# Connectors.net
KiCad netlist of a schematic drawn in Altium Designer
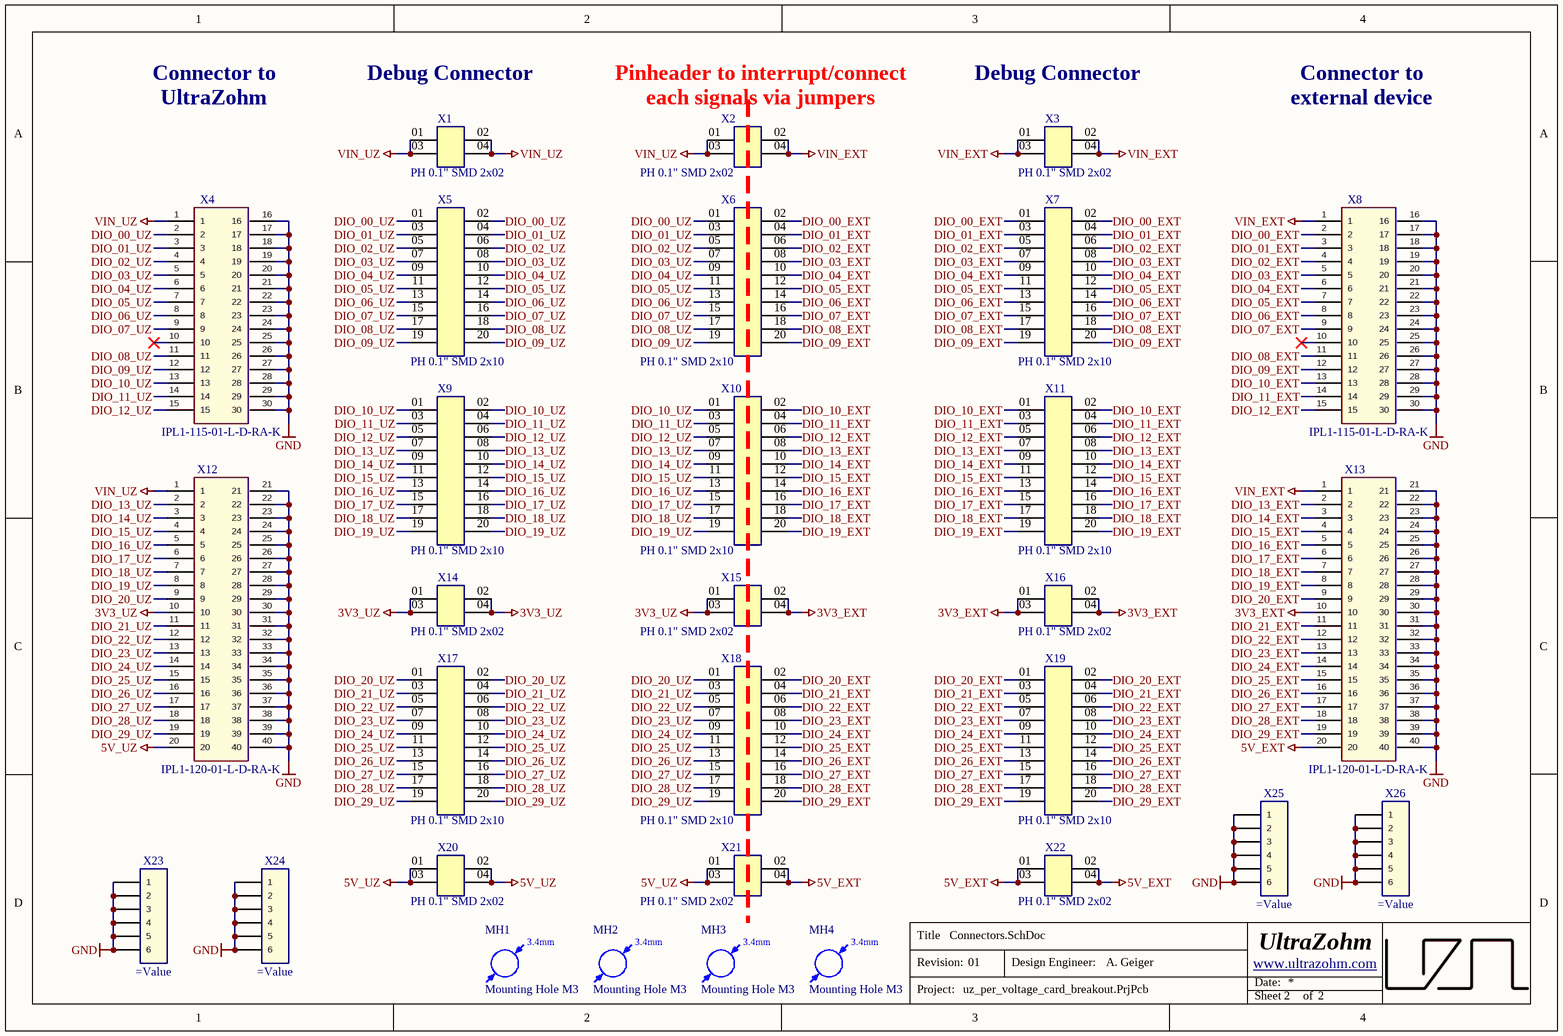
[diagram p0: Connectors.SchDoc]

(export (version "E")
  (design (tool "Eeschema 10.0.6"))
  (components
    (comp (ref "MH1")
      (value "Mounting Hole M3")
      (footprint "MH_3.4")
      (description "Mounting Hole")
      (fields (field (name "CREATED FROM") "MHlatky"))
      (libsource (lib "user") (part "Mounting Hole"))
    )
    (comp (ref "MH2")
      (value "Mounting Hole M3")
      (footprint "MH_3.4")
      (description "Mounting Hole")
      (fields (field (name "CREATED FROM") "MHlatky"))
      (libsource (lib "user") (part "Mounting Hole"))
    )
    (comp (ref "MH3")
      (value "Mounting Hole M3")
      (footprint "MH_3.4")
      (description "Mounting Hole")
      (fields (field (name "CREATED FROM") "MHlatky"))
      (libsource (lib "user") (part "Mounting Hole"))
    )
    (comp (ref "MH4")
      (value "Mounting Hole M3")
      (footprint "MH_3.4")
      (description "Mounting Hole")
      (fields (field (name "CREATED FROM") "MHlatky"))
      (libsource (lib "user") (part "Mounting Hole"))
    )
    (comp (ref "X1")
      (value "PH 0.1\" SMD 2x02")
      (footprint "TSM-102-01-L-DV")
      (description "0.1\" Double-row Pin Header, 90°-to-PCB SMD, 2x02 Pins, 250V, 3A")
      (fields
        (field (name "MANUFACTURER PART NUMBER") "UZgen_Conn_PinHead_2x02_SMD_100mil_90deg")
        (field (name "MANUFACTURER") "UZgen")
        (field (name "CREATED FROM") "UZgenTool")
      )
      (libsource (lib "user") (part "PinHeader_2x02"))
    )
    (comp (ref "X2")
      (value "PH 0.1\" SMD 2x02")
      (footprint "TSM-102-01-L-DV")
      (description "0.1\" Double-row Pin Header, 90°-to-PCB SMD, 2x02 Pins, 250V, 3A")
      (fields
        (field (name "MANUFACTURER PART NUMBER") "UZgen_Conn_PinHead_2x02_SMD_100mil_90deg")
        (field (name "MANUFACTURER") "UZgen")
        (field (name "CREATED FROM") "UZgenTool")
      )
      (libsource (lib "user") (part "PinHeader_2x02"))
    )
    (comp (ref "X3")
      (value "PH 0.1\" SMD 2x02")
      (footprint "TSM-102-01-L-DV")
      (description "0.1\" Double-row Pin Header, 90°-to-PCB SMD, 2x02 Pins, 250V, 3A")
      (fields
        (field (name "MANUFACTURER PART NUMBER") "UZgen_Conn_PinHead_2x02_SMD_100mil_90deg")
        (field (name "MANUFACTURER") "UZgen")
        (field (name "CREATED FROM") "UZgenTool")
      )
      (libsource (lib "user") (part "PinHeader_2x02"))
    )
    (comp (ref "X4")
      (value "IPL1-115-01-L-D-RA-K")
      (footprint "IPL1-115-01-XX-D-RA")
      (description "Terminal Assembly, Double Row, Right Angle, Thru-Hole, 2.54 mm x 2.54 mm Pitch, 30 Pins")
      (fields (field (name "MANUFACTURER") "SAMTEC") (field (name "CREATED FROM") "TWendt"))
      (libsource (lib "user") (part "IPL1-115-01-XX-D-RA"))
    )
    (comp (ref "X5")
      (value "PH 0.1\" SMD 2x10")
      (footprint "TSM-110-01-L-DV")
      (description "0.1\" Double-row Pin Header, 90°-to-PCB SMD, 2x10 Pins, 250V, 3A")
      (fields
        (field (name "MANUFACTURER PART NUMBER") "UZgen_Conn_PinHead_2x10_SMD_100mil_90deg")
        (field (name "MANUFACTURER") "UZgen")
        (field (name "CREATED FROM") "UZgenTool")
      )
      (libsource (lib "user") (part "PinHeader_2x10"))
    )
    (comp (ref "X6")
      (value "PH 0.1\" SMD 2x10")
      (footprint "TSM-110-01-L-DV")
      (description "0.1\" Double-row Pin Header, 90°-to-PCB SMD, 2x10 Pins, 250V, 3A")
      (fields
        (field (name "MANUFACTURER PART NUMBER") "UZgen_Conn_PinHead_2x10_SMD_100mil_90deg")
        (field (name "MANUFACTURER") "UZgen")
        (field (name "CREATED FROM") "UZgenTool")
      )
      (libsource (lib "user") (part "PinHeader_2x10"))
    )
    (comp (ref "X7")
      (value "PH 0.1\" SMD 2x10")
      (footprint "TSM-110-01-L-DV")
      (description "0.1\" Double-row Pin Header, 90°-to-PCB SMD, 2x10 Pins, 250V, 3A")
      (fields
        (field (name "MANUFACTURER PART NUMBER") "UZgen_Conn_PinHead_2x10_SMD_100mil_90deg")
        (field (name "MANUFACTURER") "UZgen")
        (field (name "CREATED FROM") "UZgenTool")
      )
      (libsource (lib "user") (part "PinHeader_2x10"))
    )
    (comp (ref "X8")
      (value "IPL1-115-01-L-D-RA-K")
      (footprint "IPL1-115-01-XX-D-RA")
      (description "Terminal Assembly, Double Row, Right Angle, Thru-Hole, 2.54 mm x 2.54 mm Pitch, 30 Pins")
      (fields (field (name "MANUFACTURER") "SAMTEC") (field (name "CREATED FROM") "TWendt"))
      (libsource (lib "user") (part "IPL1-115-01-XX-D-RA"))
    )
    (comp (ref "X9")
      (value "PH 0.1\" SMD 2x10")
      (footprint "TSM-110-01-L-DV")
      (description "0.1\" Double-row Pin Header, 90°-to-PCB SMD, 2x10 Pins, 250V, 3A")
      (fields
        (field (name "MANUFACTURER PART NUMBER") "UZgen_Conn_PinHead_2x10_SMD_100mil_90deg")
        (field (name "MANUFACTURER") "UZgen")
        (field (name "CREATED FROM") "UZgenTool")
      )
      (libsource (lib "user") (part "PinHeader_2x10"))
    )
    (comp (ref "X10")
      (value "PH 0.1\" SMD 2x10")
      (footprint "TSM-110-01-L-DV")
      (description "0.1\" Double-row Pin Header, 90°-to-PCB SMD, 2x10 Pins, 250V, 3A")
      (fields
        (field (name "MANUFACTURER PART NUMBER") "UZgen_Conn_PinHead_2x10_SMD_100mil_90deg")
        (field (name "MANUFACTURER") "UZgen")
        (field (name "CREATED FROM") "UZgenTool")
      )
      (libsource (lib "user") (part "PinHeader_2x10"))
    )
    (comp (ref "X11")
      (value "PH 0.1\" SMD 2x10")
      (footprint "TSM-110-01-L-DV")
      (description "0.1\" Double-row Pin Header, 90°-to-PCB SMD, 2x10 Pins, 250V, 3A")
      (fields
        (field (name "MANUFACTURER PART NUMBER") "UZgen_Conn_PinHead_2x10_SMD_100mil_90deg")
        (field (name "MANUFACTURER") "UZgen")
        (field (name "CREATED FROM") "UZgenTool")
      )
      (libsource (lib "user") (part "PinHeader_2x10"))
    )
    (comp (ref "X12")
      (value "IPL1-120-01-L-D-RA-K")
      (footprint "IPL1-120-01-XX-D-RA")
      (description "Terminal Assembly, Double Row, Right Angle, Thru-Hole, 2.54 mm x 2.54 mm Pitch, 40 Pins")
      (fields (field (name "MANUFACTURER") "SAMTEC") (field (name "CREATED FROM") "TWendt"))
      (libsource (lib "user") (part "IPL1-120-01-XX-D-RA"))
    )
    (comp (ref "X13")
      (value "IPL1-120-01-L-D-RA-K")
      (footprint "IPL1-120-01-XX-D-RA")
      (description "Terminal Assembly, Double Row, Right Angle, Thru-Hole, 2.54 mm x 2.54 mm Pitch, 40 Pins")
      (fields (field (name "MANUFACTURER") "SAMTEC") (field (name "CREATED FROM") "TWendt"))
      (libsource (lib "user") (part "IPL1-120-01-XX-D-RA"))
    )
    (comp (ref "X14")
      (value "PH 0.1\" SMD 2x02")
      (footprint "TSM-102-01-L-DV")
      (description "0.1\" Double-row Pin Header, 90°-to-PCB SMD, 2x02 Pins, 250V, 3A")
      (fields
        (field (name "MANUFACTURER PART NUMBER") "UZgen_Conn_PinHead_2x02_SMD_100mil_90deg")
        (field (name "MANUFACTURER") "UZgen")
        (field (name "CREATED FROM") "UZgenTool")
      )
      (libsource (lib "user") (part "PinHeader_2x02"))
    )
    (comp (ref "X15")
      (value "PH 0.1\" SMD 2x02")
      (footprint "TSM-102-01-L-DV")
      (description "0.1\" Double-row Pin Header, 90°-to-PCB SMD, 2x02 Pins, 250V, 3A")
      (fields
        (field (name "MANUFACTURER PART NUMBER") "UZgen_Conn_PinHead_2x02_SMD_100mil_90deg")
        (field (name "MANUFACTURER") "UZgen")
        (field (name "CREATED FROM") "UZgenTool")
      )
      (libsource (lib "user") (part "PinHeader_2x02"))
    )
    (comp (ref "X16")
      (value "PH 0.1\" SMD 2x02")
      (footprint "TSM-102-01-L-DV")
      (description "0.1\" Double-row Pin Header, 90°-to-PCB SMD, 2x02 Pins, 250V, 3A")
      (fields
        (field (name "MANUFACTURER PART NUMBER") "UZgen_Conn_PinHead_2x02_SMD_100mil_90deg")
        (field (name "MANUFACTURER") "UZgen")
        (field (name "CREATED FROM") "UZgenTool")
      )
      (libsource (lib "user") (part "PinHeader_2x02"))
    )
    (comp (ref "X17")
      (value "PH 0.1\" SMD 2x10")
      (footprint "TSM-110-01-L-DV")
      (description "0.1\" Double-row Pin Header, 90°-to-PCB SMD, 2x10 Pins, 250V, 3A")
      (fields
        (field (name "MANUFACTURER PART NUMBER") "UZgen_Conn_PinHead_2x10_SMD_100mil_90deg")
        (field (name "MANUFACTURER") "UZgen")
        (field (name "CREATED FROM") "UZgenTool")
      )
      (libsource (lib "user") (part "PinHeader_2x10"))
    )
    (comp (ref "X18")
      (value "PH 0.1\" SMD 2x10")
      (footprint "TSM-110-01-L-DV")
      (description "0.1\" Double-row Pin Header, 90°-to-PCB SMD, 2x10 Pins, 250V, 3A")
      (fields
        (field (name "MANUFACTURER PART NUMBER") "UZgen_Conn_PinHead_2x10_SMD_100mil_90deg")
        (field (name "MANUFACTURER") "UZgen")
        (field (name "CREATED FROM") "UZgenTool")
      )
      (libsource (lib "user") (part "PinHeader_2x10"))
    )
    (comp (ref "X19")
      (value "PH 0.1\" SMD 2x10")
      (footprint "TSM-110-01-L-DV")
      (description "0.1\" Double-row Pin Header, 90°-to-PCB SMD, 2x10 Pins, 250V, 3A")
      (fields
        (field (name "MANUFACTURER PART NUMBER") "UZgen_Conn_PinHead_2x10_SMD_100mil_90deg")
        (field (name "MANUFACTURER") "UZgen")
        (field (name "CREATED FROM") "UZgenTool")
      )
      (libsource (lib "user") (part "PinHeader_2x10"))
    )
    (comp (ref "X20")
      (value "PH 0.1\" SMD 2x02")
      (footprint "TSM-102-01-L-DV")
      (description "0.1\" Double-row Pin Header, 90°-to-PCB SMD, 2x02 Pins, 250V, 3A")
      (fields
        (field (name "MANUFACTURER PART NUMBER") "UZgen_Conn_PinHead_2x02_SMD_100mil_90deg")
        (field (name "MANUFACTURER") "UZgen")
        (field (name "CREATED FROM") "UZgenTool")
      )
      (libsource (lib "user") (part "PinHeader_2x02"))
    )
    (comp (ref "X21")
      (value "PH 0.1\" SMD 2x02")
      (footprint "TSM-102-01-L-DV")
      (description "0.1\" Double-row Pin Header, 90°-to-PCB SMD, 2x02 Pins, 250V, 3A")
      (fields
        (field (name "MANUFACTURER PART NUMBER") "UZgen_Conn_PinHead_2x02_SMD_100mil_90deg")
        (field (name "MANUFACTURER") "UZgen")
        (field (name "CREATED FROM") "UZgenTool")
      )
      (libsource (lib "user") (part "PinHeader_2x02"))
    )
    (comp (ref "X22")
      (value "PH 0.1\" SMD 2x02")
      (footprint "TSM-102-01-L-DV")
      (description "0.1\" Double-row Pin Header, 90°-to-PCB SMD, 2x02 Pins, 250V, 3A")
      (fields
        (field (name "MANUFACTURER PART NUMBER") "UZgen_Conn_PinHead_2x02_SMD_100mil_90deg")
        (field (name "MANUFACTURER") "UZgen")
        (field (name "CREATED FROM") "UZgenTool")
      )
      (libsource (lib "user") (part "PinHeader_2x02"))
    )
    (comp (ref "X23")
      (value "~")
      (footprint "TSW-106-XX-XXX-S")
      (description "Classic PCB Header Strips, 0.100\" pitch")
      (fields
        (field (name "MF") "SAMTEC")
        (field (name "MPN") "TSW-106-07-F-S")
        (field (name "CREATED") "2020_12_15_AGeiger")
        (field (name "CREATED FROM") "AGeiger")
      )
      (libsource (lib "user") (part "TSW-106-XX-XXX-S"))
    )
    (comp (ref "X24")
      (value "~")
      (footprint "TSW-106-XX-XXX-S")
      (description "Classic PCB Header Strips, 0.100\" pitch")
      (fields
        (field (name "MF") "SAMTEC")
        (field (name "MPN") "TSW-106-07-F-S")
        (field (name "CREATED") "2020_12_15_AGeiger")
        (field (name "CREATED FROM") "AGeiger")
      )
      (libsource (lib "user") (part "TSW-106-XX-XXX-S"))
    )
    (comp (ref "X25")
      (value "~")
      (footprint "TSW-106-XX-XXX-S")
      (description "Classic PCB Header Strips, 0.100\" pitch")
      (fields
        (field (name "MF") "SAMTEC")
        (field (name "MPN") "TSW-106-07-F-S")
        (field (name "CREATED") "2020_12_15_AGeiger")
        (field (name "CREATED FROM") "AGeiger")
      )
      (libsource (lib "user") (part "TSW-106-XX-XXX-S"))
    )
    (comp (ref "X26")
      (value "~")
      (footprint "TSW-106-XX-XXX-S")
      (description "Classic PCB Header Strips, 0.100\" pitch")
      (fields
        (field (name "MF") "SAMTEC")
        (field (name "MPN") "TSW-106-07-F-S")
        (field (name "CREATED") "2020_12_15_AGeiger")
        (field (name "CREATED FROM") "AGeiger")
      )
      (libsource (lib "user") (part "TSW-106-XX-XXX-S"))
    )
  )
  (nets
    (net (code "1") (name "/DIO_00_EXT") (class "Default")
      (node (ref "X6") (pin "02") (pinfunction "02_02") (pintype "passive"))
      (node (ref "X7") (pin "01") (pinfunction "01_01") (pintype "passive"))
      (node (ref "X7") (pin "02") (pinfunction "02_02") (pintype "passive"))
      (node (ref "X8") (pin "2") (pinfunction "2_2") (pintype "passive"))
    )
    (net (code "2") (name "/DIO_00_UZ") (class "Default")
      (node (ref "X4") (pin "2") (pinfunction "2_2") (pintype "passive"))
      (node (ref "X5") (pin "01") (pinfunction "01_01") (pintype "passive"))
      (node (ref "X5") (pin "02") (pinfunction "02_02") (pintype "passive"))
      (node (ref "X6") (pin "01") (pinfunction "01_01") (pintype "passive"))
    )
    (net (code "3") (name "/DIO_01_EXT") (class "Default")
      (node (ref "X6") (pin "04") (pinfunction "04_04") (pintype "passive"))
      (node (ref "X7") (pin "03") (pinfunction "03_03") (pintype "passive"))
      (node (ref "X7") (pin "04") (pinfunction "04_04") (pintype "passive"))
      (node (ref "X8") (pin "3") (pinfunction "3_3") (pintype "passive"))
    )
    (net (code "4") (name "/DIO_01_UZ") (class "Default")
      (node (ref "X4") (pin "3") (pinfunction "3_3") (pintype "passive"))
      (node (ref "X5") (pin "03") (pinfunction "03_03") (pintype "passive"))
      (node (ref "X5") (pin "04") (pinfunction "04_04") (pintype "passive"))
      (node (ref "X6") (pin "03") (pinfunction "03_03") (pintype "passive"))
    )
    (net (code "5") (name "/DIO_02_EXT") (class "Default")
      (node (ref "X6") (pin "06") (pinfunction "06_06") (pintype "passive"))
      (node (ref "X7") (pin "05") (pinfunction "05_05") (pintype "passive"))
      (node (ref "X7") (pin "06") (pinfunction "06_06") (pintype "passive"))
      (node (ref "X8") (pin "4") (pinfunction "4_4") (pintype "passive"))
    )
    (net (code "6") (name "/DIO_02_UZ") (class "Default")
      (node (ref "X4") (pin "4") (pinfunction "4_4") (pintype "passive"))
      (node (ref "X5") (pin "05") (pinfunction "05_05") (pintype "passive"))
      (node (ref "X5") (pin "06") (pinfunction "06_06") (pintype "passive"))
      (node (ref "X6") (pin "05") (pinfunction "05_05") (pintype "passive"))
    )
    (net (code "7") (name "/DIO_03_EXT") (class "Default")
      (node (ref "X6") (pin "08") (pinfunction "08_08") (pintype "passive"))
      (node (ref "X7") (pin "07") (pinfunction "07_07") (pintype "passive"))
      (node (ref "X7") (pin "08") (pinfunction "08_08") (pintype "passive"))
      (node (ref "X8") (pin "5") (pinfunction "5_5") (pintype "passive"))
    )
    (net (code "8") (name "/DIO_03_UZ") (class "Default")
      (node (ref "X4") (pin "5") (pinfunction "5_5") (pintype "passive"))
      (node (ref "X5") (pin "07") (pinfunction "07_07") (pintype "passive"))
      (node (ref "X5") (pin "08") (pinfunction "08_08") (pintype "passive"))
      (node (ref "X6") (pin "07") (pinfunction "07_07") (pintype "passive"))
    )
    (net (code "9") (name "/DIO_04_EXT") (class "Default")
      (node (ref "X6") (pin "10") (pinfunction "10_10") (pintype "passive"))
      (node (ref "X7") (pin "09") (pinfunction "09_09") (pintype "passive"))
      (node (ref "X7") (pin "10") (pinfunction "10_10") (pintype "passive"))
      (node (ref "X8") (pin "6") (pinfunction "6_6") (pintype "passive"))
    )
    (net (code "10") (name "/DIO_04_UZ") (class "Default")
      (node (ref "X4") (pin "6") (pinfunction "6_6") (pintype "passive"))
      (node (ref "X5") (pin "09") (pinfunction "09_09") (pintype "passive"))
      (node (ref "X5") (pin "10") (pinfunction "10_10") (pintype "passive"))
      (node (ref "X6") (pin "09") (pinfunction "09_09") (pintype "passive"))
    )
    (net (code "11") (name "/DIO_05_EXT") (class "Default")
      (node (ref "X6") (pin "12") (pinfunction "12_12") (pintype "passive"))
      (node (ref "X7") (pin "11") (pinfunction "11_11") (pintype "passive"))
      (node (ref "X7") (pin "12") (pinfunction "12_12") (pintype "passive"))
      (node (ref "X8") (pin "7") (pinfunction "7_7") (pintype "passive"))
    )
    (net (code "12") (name "/DIO_05_UZ") (class "Default")
      (node (ref "X4") (pin "7") (pinfunction "7_7") (pintype "passive"))
      (node (ref "X5") (pin "11") (pinfunction "11_11") (pintype "passive"))
      (node (ref "X5") (pin "12") (pinfunction "12_12") (pintype "passive"))
      (node (ref "X6") (pin "11") (pinfunction "11_11") (pintype "passive"))
    )
    (net (code "13") (name "/DIO_06_EXT") (class "Default")
      (node (ref "X6") (pin "14") (pinfunction "14_14") (pintype "passive"))
      (node (ref "X7") (pin "13") (pinfunction "13_13") (pintype "passive"))
      (node (ref "X7") (pin "14") (pinfunction "14_14") (pintype "passive"))
      (node (ref "X8") (pin "8") (pinfunction "8_8") (pintype "passive"))
    )
    (net (code "14") (name "/DIO_06_UZ") (class "Default")
      (node (ref "X4") (pin "8") (pinfunction "8_8") (pintype "passive"))
      (node (ref "X5") (pin "13") (pinfunction "13_13") (pintype "passive"))
      (node (ref "X5") (pin "14") (pinfunction "14_14") (pintype "passive"))
      (node (ref "X6") (pin "13") (pinfunction "13_13") (pintype "passive"))
    )
    (net (code "15") (name "/DIO_07_EXT") (class "Default")
      (node (ref "X6") (pin "16") (pinfunction "16_16") (pintype "passive"))
      (node (ref "X7") (pin "15") (pinfunction "15_15") (pintype "passive"))
      (node (ref "X7") (pin "16") (pinfunction "16_16") (pintype "passive"))
      (node (ref "X8") (pin "9") (pinfunction "9_9") (pintype "passive"))
    )
    (net (code "16") (name "/DIO_07_UZ") (class "Default")
      (node (ref "X4") (pin "9") (pinfunction "9_9") (pintype "passive"))
      (node (ref "X5") (pin "15") (pinfunction "15_15") (pintype "passive"))
      (node (ref "X5") (pin "16") (pinfunction "16_16") (pintype "passive"))
      (node (ref "X6") (pin "15") (pinfunction "15_15") (pintype "passive"))
    )
    (net (code "17") (name "/DIO_08_EXT") (class "Default")
      (node (ref "X6") (pin "18") (pinfunction "18_18") (pintype "passive"))
      (node (ref "X7") (pin "17") (pinfunction "17_17") (pintype "passive"))
      (node (ref "X7") (pin "18") (pinfunction "18_18") (pintype "passive"))
      (node (ref "X8") (pin "11") (pinfunction "11_11") (pintype "passive"))
    )
    (net (code "18") (name "/DIO_08_UZ") (class "Default")
      (node (ref "X4") (pin "11") (pinfunction "11_11") (pintype "passive"))
      (node (ref "X5") (pin "17") (pinfunction "17_17") (pintype "passive"))
      (node (ref "X5") (pin "18") (pinfunction "18_18") (pintype "passive"))
      (node (ref "X6") (pin "17") (pinfunction "17_17") (pintype "passive"))
    )
    (net (code "19") (name "/DIO_09_EXT") (class "Default")
      (node (ref "X6") (pin "20") (pinfunction "20_20") (pintype "passive"))
      (node (ref "X7") (pin "19") (pinfunction "19_19") (pintype "passive"))
      (node (ref "X7") (pin "20") (pinfunction "20_20") (pintype "passive"))
      (node (ref "X8") (pin "12") (pinfunction "12_12") (pintype "passive"))
    )
    (net (code "20") (name "/DIO_09_UZ") (class "Default")
      (node (ref "X4") (pin "12") (pinfunction "12_12") (pintype "passive"))
      (node (ref "X5") (pin "19") (pinfunction "19_19") (pintype "passive"))
      (node (ref "X5") (pin "20") (pinfunction "20_20") (pintype "passive"))
      (node (ref "X6") (pin "19") (pinfunction "19_19") (pintype "passive"))
    )
    (net (code "21") (name "/DIO_10_EXT") (class "Default")
      (node (ref "X10") (pin "02") (pinfunction "02_02") (pintype "passive"))
      (node (ref "X11") (pin "01") (pinfunction "01_01") (pintype "passive"))
      (node (ref "X11") (pin "02") (pinfunction "02_02") (pintype "passive"))
      (node (ref "X8") (pin "13") (pinfunction "13_13") (pintype "passive"))
    )
    (net (code "22") (name "/DIO_10_UZ") (class "Default")
      (node (ref "X10") (pin "01") (pinfunction "01_01") (pintype "passive"))
      (node (ref "X4") (pin "13") (pinfunction "13_13") (pintype "passive"))
      (node (ref "X9") (pin "01") (pinfunction "01_01") (pintype "passive"))
      (node (ref "X9") (pin "02") (pinfunction "02_02") (pintype "passive"))
    )
    (net (code "23") (name "/DIO_11_EXT") (class "Default")
      (node (ref "X10") (pin "04") (pinfunction "04_04") (pintype "passive"))
      (node (ref "X11") (pin "03") (pinfunction "03_03") (pintype "passive"))
      (node (ref "X11") (pin "04") (pinfunction "04_04") (pintype "passive"))
      (node (ref "X8") (pin "14") (pinfunction "14_14") (pintype "passive"))
    )
    (net (code "24") (name "/DIO_11_UZ") (class "Default")
      (node (ref "X10") (pin "03") (pinfunction "03_03") (pintype "passive"))
      (node (ref "X4") (pin "14") (pinfunction "14_14") (pintype "passive"))
      (node (ref "X9") (pin "03") (pinfunction "03_03") (pintype "passive"))
      (node (ref "X9") (pin "04") (pinfunction "04_04") (pintype "passive"))
    )
    (net (code "25") (name "/DIO_12_EXT") (class "Default")
      (node (ref "X10") (pin "06") (pinfunction "06_06") (pintype "passive"))
      (node (ref "X11") (pin "05") (pinfunction "05_05") (pintype "passive"))
      (node (ref "X11") (pin "06") (pinfunction "06_06") (pintype "passive"))
      (node (ref "X8") (pin "15") (pinfunction "15_15") (pintype "passive"))
    )
    (net (code "26") (name "/DIO_12_UZ") (class "Default")
      (node (ref "X10") (pin "05") (pinfunction "05_05") (pintype "passive"))
      (node (ref "X4") (pin "15") (pinfunction "15_15") (pintype "passive"))
      (node (ref "X9") (pin "05") (pinfunction "05_05") (pintype "passive"))
      (node (ref "X9") (pin "06") (pinfunction "06_06") (pintype "passive"))
    )
    (net (code "27") (name "/DIO_13_EXT") (class "Default")
      (node (ref "X10") (pin "08") (pinfunction "08_08") (pintype "passive"))
      (node (ref "X11") (pin "07") (pinfunction "07_07") (pintype "passive"))
      (node (ref "X11") (pin "08") (pinfunction "08_08") (pintype "passive"))
      (node (ref "X13") (pin "2") (pinfunction "2_2") (pintype "passive"))
    )
    (net (code "28") (name "/DIO_13_UZ") (class "Default")
      (node (ref "X10") (pin "07") (pinfunction "07_07") (pintype "passive"))
      (node (ref "X12") (pin "2") (pinfunction "2_2") (pintype "passive"))
      (node (ref "X9") (pin "07") (pinfunction "07_07") (pintype "passive"))
      (node (ref "X9") (pin "08") (pinfunction "08_08") (pintype "passive"))
    )
    (net (code "29") (name "/DIO_14_EXT") (class "Default")
      (node (ref "X10") (pin "10") (pinfunction "10_10") (pintype "passive"))
      (node (ref "X11") (pin "09") (pinfunction "09_09") (pintype "passive"))
      (node (ref "X11") (pin "10") (pinfunction "10_10") (pintype "passive"))
      (node (ref "X13") (pin "3") (pinfunction "3_3") (pintype "passive"))
    )
    (net (code "30") (name "/DIO_14_UZ") (class "Default")
      (node (ref "X10") (pin "09") (pinfunction "09_09") (pintype "passive"))
      (node (ref "X12") (pin "3") (pinfunction "3_3") (pintype "passive"))
      (node (ref "X9") (pin "09") (pinfunction "09_09") (pintype "passive"))
      (node (ref "X9") (pin "10") (pinfunction "10_10") (pintype "passive"))
    )
    (net (code "31") (name "/DIO_15_EXT") (class "Default")
      (node (ref "X10") (pin "12") (pinfunction "12_12") (pintype "passive"))
      (node (ref "X11") (pin "11") (pinfunction "11_11") (pintype "passive"))
      (node (ref "X11") (pin "12") (pinfunction "12_12") (pintype "passive"))
      (node (ref "X13") (pin "4") (pinfunction "4_4") (pintype "passive"))
    )
    (net (code "32") (name "/DIO_15_UZ") (class "Default")
      (node (ref "X10") (pin "11") (pinfunction "11_11") (pintype "passive"))
      (node (ref "X12") (pin "4") (pinfunction "4_4") (pintype "passive"))
      (node (ref "X9") (pin "11") (pinfunction "11_11") (pintype "passive"))
      (node (ref "X9") (pin "12") (pinfunction "12_12") (pintype "passive"))
    )
    (net (code "33") (name "/DIO_16_EXT") (class "Default")
      (node (ref "X10") (pin "14") (pinfunction "14_14") (pintype "passive"))
      (node (ref "X11") (pin "13") (pinfunction "13_13") (pintype "passive"))
      (node (ref "X11") (pin "14") (pinfunction "14_14") (pintype "passive"))
      (node (ref "X13") (pin "5") (pinfunction "5_5") (pintype "passive"))
    )
    (net (code "34") (name "/DIO_16_UZ") (class "Default")
      (node (ref "X10") (pin "13") (pinfunction "13_13") (pintype "passive"))
      (node (ref "X12") (pin "5") (pinfunction "5_5") (pintype "passive"))
      (node (ref "X9") (pin "13") (pinfunction "13_13") (pintype "passive"))
      (node (ref "X9") (pin "14") (pinfunction "14_14") (pintype "passive"))
    )
    (net (code "35") (name "/DIO_17_EXT") (class "Default")
      (node (ref "X10") (pin "16") (pinfunction "16_16") (pintype "passive"))
      (node (ref "X11") (pin "15") (pinfunction "15_15") (pintype "passive"))
      (node (ref "X11") (pin "16") (pinfunction "16_16") (pintype "passive"))
      (node (ref "X13") (pin "6") (pinfunction "6_6") (pintype "passive"))
    )
    (net (code "36") (name "/DIO_17_UZ") (class "Default")
      (node (ref "X10") (pin "15") (pinfunction "15_15") (pintype "passive"))
      (node (ref "X12") (pin "6") (pinfunction "6_6") (pintype "passive"))
      (node (ref "X9") (pin "15") (pinfunction "15_15") (pintype "passive"))
      (node (ref "X9") (pin "16") (pinfunction "16_16") (pintype "passive"))
    )
    (net (code "37") (name "/DIO_18_EXT") (class "Default")
      (node (ref "X10") (pin "18") (pinfunction "18_18") (pintype "passive"))
      (node (ref "X11") (pin "17") (pinfunction "17_17") (pintype "passive"))
      (node (ref "X11") (pin "18") (pinfunction "18_18") (pintype "passive"))
      (node (ref "X13") (pin "7") (pinfunction "7_7") (pintype "passive"))
    )
    (net (code "38") (name "/DIO_18_UZ") (class "Default")
      (node (ref "X10") (pin "17") (pinfunction "17_17") (pintype "passive"))
      (node (ref "X12") (pin "7") (pinfunction "7_7") (pintype "passive"))
      (node (ref "X9") (pin "17") (pinfunction "17_17") (pintype "passive"))
      (node (ref "X9") (pin "18") (pinfunction "18_18") (pintype "passive"))
    )
    (net (code "39") (name "/DIO_19_EXT") (class "Default")
      (node (ref "X10") (pin "20") (pinfunction "20_20") (pintype "passive"))
      (node (ref "X11") (pin "19") (pinfunction "19_19") (pintype "passive"))
      (node (ref "X11") (pin "20") (pinfunction "20_20") (pintype "passive"))
      (node (ref "X13") (pin "8") (pinfunction "8_8") (pintype "passive"))
    )
    (net (code "40") (name "/DIO_19_UZ") (class "Default")
      (node (ref "X10") (pin "19") (pinfunction "19_19") (pintype "passive"))
      (node (ref "X12") (pin "8") (pinfunction "8_8") (pintype "passive"))
      (node (ref "X9") (pin "19") (pinfunction "19_19") (pintype "passive"))
      (node (ref "X9") (pin "20") (pinfunction "20_20") (pintype "passive"))
    )
    (net (code "41") (name "/DIO_20_EXT") (class "Default")
      (node (ref "X13") (pin "9") (pinfunction "9_9") (pintype "passive"))
      (node (ref "X18") (pin "02") (pinfunction "02_02") (pintype "passive"))
      (node (ref "X19") (pin "01") (pinfunction "01_01") (pintype "passive"))
      (node (ref "X19") (pin "02") (pinfunction "02_02") (pintype "passive"))
    )
    (net (code "42") (name "/DIO_20_UZ") (class "Default")
      (node (ref "X12") (pin "9") (pinfunction "9_9") (pintype "passive"))
      (node (ref "X17") (pin "01") (pinfunction "01_01") (pintype "passive"))
      (node (ref "X17") (pin "02") (pinfunction "02_02") (pintype "passive"))
      (node (ref "X18") (pin "01") (pinfunction "01_01") (pintype "passive"))
    )
    (net (code "43") (name "/DIO_21_EXT") (class "Default")
      (node (ref "X13") (pin "11") (pinfunction "11_11") (pintype "passive"))
      (node (ref "X18") (pin "04") (pinfunction "04_04") (pintype "passive"))
      (node (ref "X19") (pin "03") (pinfunction "03_03") (pintype "passive"))
      (node (ref "X19") (pin "04") (pinfunction "04_04") (pintype "passive"))
    )
    (net (code "44") (name "/DIO_21_UZ") (class "Default")
      (node (ref "X12") (pin "11") (pinfunction "11_11") (pintype "passive"))
      (node (ref "X17") (pin "03") (pinfunction "03_03") (pintype "passive"))
      (node (ref "X17") (pin "04") (pinfunction "04_04") (pintype "passive"))
      (node (ref "X18") (pin "03") (pinfunction "03_03") (pintype "passive"))
    )
    (net (code "45") (name "/DIO_22_EXT") (class "Default")
      (node (ref "X13") (pin "12") (pinfunction "12_12") (pintype "passive"))
      (node (ref "X18") (pin "06") (pinfunction "06_06") (pintype "passive"))
      (node (ref "X19") (pin "05") (pinfunction "05_05") (pintype "passive"))
      (node (ref "X19") (pin "06") (pinfunction "06_06") (pintype "passive"))
    )
    (net (code "46") (name "/DIO_22_UZ") (class "Default")
      (node (ref "X12") (pin "12") (pinfunction "12_12") (pintype "passive"))
      (node (ref "X17") (pin "05") (pinfunction "05_05") (pintype "passive"))
      (node (ref "X17") (pin "06") (pinfunction "06_06") (pintype "passive"))
      (node (ref "X18") (pin "05") (pinfunction "05_05") (pintype "passive"))
    )
    (net (code "47") (name "/DIO_23_EXT") (class "Default")
      (node (ref "X13") (pin "13") (pinfunction "13_13") (pintype "passive"))
      (node (ref "X18") (pin "08") (pinfunction "08_08") (pintype "passive"))
      (node (ref "X19") (pin "07") (pinfunction "07_07") (pintype "passive"))
      (node (ref "X19") (pin "08") (pinfunction "08_08") (pintype "passive"))
    )
    (net (code "48") (name "/DIO_23_UZ") (class "Default")
      (node (ref "X12") (pin "13") (pinfunction "13_13") (pintype "passive"))
      (node (ref "X17") (pin "07") (pinfunction "07_07") (pintype "passive"))
      (node (ref "X17") (pin "08") (pinfunction "08_08") (pintype "passive"))
      (node (ref "X18") (pin "07") (pinfunction "07_07") (pintype "passive"))
    )
    (net (code "49") (name "/DIO_24_EXT") (class "Default")
      (node (ref "X13") (pin "14") (pinfunction "14_14") (pintype "passive"))
      (node (ref "X18") (pin "10") (pinfunction "10_10") (pintype "passive"))
      (node (ref "X19") (pin "09") (pinfunction "09_09") (pintype "passive"))
      (node (ref "X19") (pin "10") (pinfunction "10_10") (pintype "passive"))
    )
    (net (code "50") (name "/DIO_24_UZ") (class "Default")
      (node (ref "X12") (pin "14") (pinfunction "14_14") (pintype "passive"))
      (node (ref "X17") (pin "09") (pinfunction "09_09") (pintype "passive"))
      (node (ref "X17") (pin "10") (pinfunction "10_10") (pintype "passive"))
      (node (ref "X18") (pin "09") (pinfunction "09_09") (pintype "passive"))
    )
    (net (code "51") (name "/DIO_25_EXT") (class "Default")
      (node (ref "X13") (pin "15") (pinfunction "15_15") (pintype "passive"))
      (node (ref "X18") (pin "12") (pinfunction "12_12") (pintype "passive"))
      (node (ref "X19") (pin "11") (pinfunction "11_11") (pintype "passive"))
      (node (ref "X19") (pin "12") (pinfunction "12_12") (pintype "passive"))
    )
    (net (code "52") (name "/DIO_25_UZ") (class "Default")
      (node (ref "X12") (pin "15") (pinfunction "15_15") (pintype "passive"))
      (node (ref "X17") (pin "11") (pinfunction "11_11") (pintype "passive"))
      (node (ref "X17") (pin "12") (pinfunction "12_12") (pintype "passive"))
      (node (ref "X18") (pin "11") (pinfunction "11_11") (pintype "passive"))
    )
    (net (code "53") (name "/DIO_26_EXT") (class "Default")
      (node (ref "X13") (pin "16") (pinfunction "16_16") (pintype "passive"))
      (node (ref "X18") (pin "14") (pinfunction "14_14") (pintype "passive"))
      (node (ref "X19") (pin "13") (pinfunction "13_13") (pintype "passive"))
      (node (ref "X19") (pin "14") (pinfunction "14_14") (pintype "passive"))
    )
    (net (code "54") (name "/DIO_26_UZ") (class "Default")
      (node (ref "X12") (pin "16") (pinfunction "16_16") (pintype "passive"))
      (node (ref "X17") (pin "13") (pinfunction "13_13") (pintype "passive"))
      (node (ref "X17") (pin "14") (pinfunction "14_14") (pintype "passive"))
      (node (ref "X18") (pin "13") (pinfunction "13_13") (pintype "passive"))
    )
    (net (code "55") (name "/DIO_27_EXT") (class "Default")
      (node (ref "X13") (pin "17") (pinfunction "17_17") (pintype "passive"))
      (node (ref "X18") (pin "16") (pinfunction "16_16") (pintype "passive"))
      (node (ref "X19") (pin "15") (pinfunction "15_15") (pintype "passive"))
      (node (ref "X19") (pin "16") (pinfunction "16_16") (pintype "passive"))
    )
    (net (code "56") (name "/DIO_27_UZ") (class "Default")
      (node (ref "X12") (pin "17") (pinfunction "17_17") (pintype "passive"))
      (node (ref "X17") (pin "15") (pinfunction "15_15") (pintype "passive"))
      (node (ref "X17") (pin "16") (pinfunction "16_16") (pintype "passive"))
      (node (ref "X18") (pin "15") (pinfunction "15_15") (pintype "passive"))
    )
    (net (code "57") (name "/DIO_28_EXT") (class "Default")
      (node (ref "X13") (pin "18") (pinfunction "18_18") (pintype "passive"))
      (node (ref "X18") (pin "18") (pinfunction "18_18") (pintype "passive"))
      (node (ref "X19") (pin "17") (pinfunction "17_17") (pintype "passive"))
      (node (ref "X19") (pin "18") (pinfunction "18_18") (pintype "passive"))
    )
    (net (code "58") (name "/DIO_28_UZ") (class "Default")
      (node (ref "X12") (pin "18") (pinfunction "18_18") (pintype "passive"))
      (node (ref "X17") (pin "17") (pinfunction "17_17") (pintype "passive"))
      (node (ref "X17") (pin "18") (pinfunction "18_18") (pintype "passive"))
      (node (ref "X18") (pin "17") (pinfunction "17_17") (pintype "passive"))
    )
    (net (code "59") (name "/DIO_29_EXT") (class "Default")
      (node (ref "X13") (pin "19") (pinfunction "19_19") (pintype "passive"))
      (node (ref "X18") (pin "20") (pinfunction "20_20") (pintype "passive"))
      (node (ref "X19") (pin "19") (pinfunction "19_19") (pintype "passive"))
      (node (ref "X19") (pin "20") (pinfunction "20_20") (pintype "passive"))
    )
    (net (code "60") (name "/DIO_29_UZ") (class "Default")
      (node (ref "X12") (pin "19") (pinfunction "19_19") (pintype "passive"))
      (node (ref "X17") (pin "19") (pinfunction "19_19") (pintype "passive"))
      (node (ref "X17") (pin "20") (pinfunction "20_20") (pintype "passive"))
      (node (ref "X18") (pin "19") (pinfunction "19_19") (pintype "passive"))
    )
    (net (code "61") (name "3V3_EXT") (class "Default")
      (node (ref "X13") (pin "10") (pinfunction "10_10") (pintype "passive"))
      (node (ref "X15") (pin "02") (pinfunction "02_02") (pintype "passive"))
      (node (ref "X15") (pin "04") (pinfunction "04_04") (pintype "passive"))
      (node (ref "X16") (pin "01") (pinfunction "01_01") (pintype "passive"))
      (node (ref "X16") (pin "02") (pinfunction "02_02") (pintype "passive"))
      (node (ref "X16") (pin "03") (pinfunction "03_03") (pintype "passive"))
      (node (ref "X16") (pin "04") (pinfunction "04_04") (pintype "passive"))
    )
    (net (code "62") (name "3V3_UZ") (class "Default")
      (node (ref "X12") (pin "10") (pinfunction "10_10") (pintype "passive"))
      (node (ref "X14") (pin "01") (pinfunction "01_01") (pintype "passive"))
      (node (ref "X14") (pin "02") (pinfunction "02_02") (pintype "passive"))
      (node (ref "X14") (pin "03") (pinfunction "03_03") (pintype "passive"))
      (node (ref "X14") (pin "04") (pinfunction "04_04") (pintype "passive"))
      (node (ref "X15") (pin "01") (pinfunction "01_01") (pintype "passive"))
      (node (ref "X15") (pin "03") (pinfunction "03_03") (pintype "passive"))
    )
    (net (code "63") (name "5V_EXT") (class "Default")
      (node (ref "X13") (pin "20") (pinfunction "20_20") (pintype "passive"))
      (node (ref "X21") (pin "02") (pinfunction "02_02") (pintype "passive"))
      (node (ref "X21") (pin "04") (pinfunction "04_04") (pintype "passive"))
      (node (ref "X22") (pin "01") (pinfunction "01_01") (pintype "passive"))
      (node (ref "X22") (pin "02") (pinfunction "02_02") (pintype "passive"))
      (node (ref "X22") (pin "03") (pinfunction "03_03") (pintype "passive"))
      (node (ref "X22") (pin "04") (pinfunction "04_04") (pintype "passive"))
    )
    (net (code "64") (name "5V_UZ") (class "Default")
      (node (ref "X12") (pin "20") (pinfunction "20_20") (pintype "passive"))
      (node (ref "X20") (pin "01") (pinfunction "01_01") (pintype "passive"))
      (node (ref "X20") (pin "02") (pinfunction "02_02") (pintype "passive"))
      (node (ref "X20") (pin "03") (pinfunction "03_03") (pintype "passive"))
      (node (ref "X20") (pin "04") (pinfunction "04_04") (pintype "passive"))
      (node (ref "X21") (pin "01") (pinfunction "01_01") (pintype "passive"))
      (node (ref "X21") (pin "03") (pinfunction "03_03") (pintype "passive"))
    )
    (net (code "65") (name "GND") (class "Default")
      (node (ref "X12") (pin "21") (pinfunction "21_21") (pintype "passive"))
      (node (ref "X12") (pin "22") (pinfunction "22_22") (pintype "passive"))
      (node (ref "X12") (pin "23") (pinfunction "23_23") (pintype "passive"))
      (node (ref "X12") (pin "24") (pinfunction "24_24") (pintype "passive"))
      (node (ref "X12") (pin "25") (pinfunction "25_25") (pintype "passive"))
      (node (ref "X12") (pin "26") (pinfunction "26_26") (pintype "passive"))
      (node (ref "X12") (pin "27") (pinfunction "27_27") (pintype "passive"))
      (node (ref "X12") (pin "28") (pinfunction "28_28") (pintype "passive"))
      (node (ref "X12") (pin "29") (pinfunction "29_29") (pintype "passive"))
      (node (ref "X12") (pin "30") (pinfunction "30_30") (pintype "passive"))
      (node (ref "X12") (pin "31") (pinfunction "31_31") (pintype "passive"))
      (node (ref "X12") (pin "32") (pinfunction "32_32") (pintype "passive"))
      (node (ref "X12") (pin "33") (pinfunction "33_33") (pintype "passive"))
      (node (ref "X12") (pin "34") (pinfunction "34_34") (pintype "passive"))
      (node (ref "X12") (pin "35") (pinfunction "35_35") (pintype "passive"))
      (node (ref "X12") (pin "36") (pinfunction "36_36") (pintype "passive"))
      (node (ref "X12") (pin "37") (pinfunction "37_37") (pintype "passive"))
      (node (ref "X12") (pin "38") (pinfunction "38_38") (pintype "passive"))
      (node (ref "X12") (pin "39") (pinfunction "39_39") (pintype "passive"))
      (node (ref "X12") (pin "40") (pinfunction "40_40") (pintype "passive"))
      (node (ref "X13") (pin "21") (pinfunction "21_21") (pintype "passive"))
      (node (ref "X13") (pin "22") (pinfunction "22_22") (pintype "passive"))
      (node (ref "X13") (pin "23") (pinfunction "23_23") (pintype "passive"))
      (node (ref "X13") (pin "24") (pinfunction "24_24") (pintype "passive"))
      (node (ref "X13") (pin "25") (pinfunction "25_25") (pintype "passive"))
      (node (ref "X13") (pin "26") (pinfunction "26_26") (pintype "passive"))
      (node (ref "X13") (pin "27") (pinfunction "27_27") (pintype "passive"))
      (node (ref "X13") (pin "28") (pinfunction "28_28") (pintype "passive"))
      (node (ref "X13") (pin "29") (pinfunction "29_29") (pintype "passive"))
      (node (ref "X13") (pin "30") (pinfunction "30_30") (pintype "passive"))
      (node (ref "X13") (pin "31") (pinfunction "31_31") (pintype "passive"))
      (node (ref "X13") (pin "32") (pinfunction "32_32") (pintype "passive"))
      (node (ref "X13") (pin "33") (pinfunction "33_33") (pintype "passive"))
      (node (ref "X13") (pin "34") (pinfunction "34_34") (pintype "passive"))
      (node (ref "X13") (pin "35") (pinfunction "35_35") (pintype "passive"))
      (node (ref "X13") (pin "36") (pinfunction "36_36") (pintype "passive"))
      (node (ref "X13") (pin "37") (pinfunction "37_37") (pintype "passive"))
      (node (ref "X13") (pin "38") (pinfunction "38_38") (pintype "passive"))
      (node (ref "X13") (pin "39") (pinfunction "39_39") (pintype "passive"))
      (node (ref "X13") (pin "40") (pinfunction "40_40") (pintype "passive"))
      (node (ref "X23") (pin "1") (pinfunction "1_1") (pintype "passive"))
      (node (ref "X23") (pin "2") (pinfunction "2_2") (pintype "passive"))
      (node (ref "X23") (pin "3") (pinfunction "3_3") (pintype "passive"))
      (node (ref "X23") (pin "4") (pinfunction "4_4") (pintype "passive"))
      (node (ref "X23") (pin "5") (pinfunction "5_5") (pintype "passive"))
      (node (ref "X23") (pin "6") (pinfunction "6_6") (pintype "passive"))
      (node (ref "X24") (pin "1") (pinfunction "1_1") (pintype "passive"))
      (node (ref "X24") (pin "2") (pinfunction "2_2") (pintype "passive"))
      (node (ref "X24") (pin "3") (pinfunction "3_3") (pintype "passive"))
      (node (ref "X24") (pin "4") (pinfunction "4_4") (pintype "passive"))
      (node (ref "X24") (pin "5") (pinfunction "5_5") (pintype "passive"))
      (node (ref "X24") (pin "6") (pinfunction "6_6") (pintype "passive"))
      (node (ref "X25") (pin "1") (pinfunction "1_1") (pintype "passive"))
      (node (ref "X25") (pin "2") (pinfunction "2_2") (pintype "passive"))
      (node (ref "X25") (pin "3") (pinfunction "3_3") (pintype "passive"))
      (node (ref "X25") (pin "4") (pinfunction "4_4") (pintype "passive"))
      (node (ref "X25") (pin "5") (pinfunction "5_5") (pintype "passive"))
      (node (ref "X25") (pin "6") (pinfunction "6_6") (pintype "passive"))
      (node (ref "X26") (pin "1") (pinfunction "1_1") (pintype "passive"))
      (node (ref "X26") (pin "2") (pinfunction "2_2") (pintype "passive"))
      (node (ref "X26") (pin "3") (pinfunction "3_3") (pintype "passive"))
      (node (ref "X26") (pin "4") (pinfunction "4_4") (pintype "passive"))
      (node (ref "X26") (pin "5") (pinfunction "5_5") (pintype "passive"))
      (node (ref "X26") (pin "6") (pinfunction "6_6") (pintype "passive"))
      (node (ref "X4") (pin "16") (pinfunction "16_16") (pintype "passive"))
      (node (ref "X4") (pin "17") (pinfunction "17_17") (pintype "passive"))
      (node (ref "X4") (pin "18") (pinfunction "18_18") (pintype "passive"))
      (node (ref "X4") (pin "19") (pinfunction "19_19") (pintype "passive"))
      (node (ref "X4") (pin "20") (pinfunction "20_20") (pintype "passive"))
      (node (ref "X4") (pin "21") (pinfunction "21_21") (pintype "passive"))
      (node (ref "X4") (pin "22") (pinfunction "22_22") (pintype "passive"))
      (node (ref "X4") (pin "23") (pinfunction "23_23") (pintype "passive"))
      (node (ref "X4") (pin "24") (pinfunction "24_24") (pintype "passive"))
      (node (ref "X4") (pin "25") (pinfunction "25_25") (pintype "passive"))
      (node (ref "X4") (pin "26") (pinfunction "26_26") (pintype "passive"))
      (node (ref "X4") (pin "27") (pinfunction "27_27") (pintype "passive"))
      (node (ref "X4") (pin "28") (pinfunction "28_28") (pintype "passive"))
      (node (ref "X4") (pin "29") (pinfunction "29_29") (pintype "passive"))
      (node (ref "X4") (pin "30") (pinfunction "30_30") (pintype "passive"))
      (node (ref "X8") (pin "16") (pinfunction "16_16") (pintype "passive"))
      (node (ref "X8") (pin "17") (pinfunction "17_17") (pintype "passive"))
      (node (ref "X8") (pin "18") (pinfunction "18_18") (pintype "passive"))
      (node (ref "X8") (pin "19") (pinfunction "19_19") (pintype "passive"))
      (node (ref "X8") (pin "20") (pinfunction "20_20") (pintype "passive"))
      (node (ref "X8") (pin "21") (pinfunction "21_21") (pintype "passive"))
      (node (ref "X8") (pin "22") (pinfunction "22_22") (pintype "passive"))
      (node (ref "X8") (pin "23") (pinfunction "23_23") (pintype "passive"))
      (node (ref "X8") (pin "24") (pinfunction "24_24") (pintype "passive"))
      (node (ref "X8") (pin "25") (pinfunction "25_25") (pintype "passive"))
      (node (ref "X8") (pin "26") (pinfunction "26_26") (pintype "passive"))
      (node (ref "X8") (pin "27") (pinfunction "27_27") (pintype "passive"))
      (node (ref "X8") (pin "28") (pinfunction "28_28") (pintype "passive"))
      (node (ref "X8") (pin "29") (pinfunction "29_29") (pintype "passive"))
      (node (ref "X8") (pin "30") (pinfunction "30_30") (pintype "passive"))
    )
    (net (code "66") (name "VIN_EXT") (class "Default")
      (node (ref "X13") (pin "1") (pinfunction "1_1") (pintype "passive"))
      (node (ref "X2") (pin "02") (pinfunction "02_02") (pintype "passive"))
      (node (ref "X2") (pin "04") (pinfunction "04_04") (pintype "passive"))
      (node (ref "X3") (pin "01") (pinfunction "01_01") (pintype "passive"))
      (node (ref "X3") (pin "02") (pinfunction "02_02") (pintype "passive"))
      (node (ref "X3") (pin "03") (pinfunction "03_03") (pintype "passive"))
      (node (ref "X3") (pin "04") (pinfunction "04_04") (pintype "passive"))
      (node (ref "X8") (pin "1") (pinfunction "1_1") (pintype "passive"))
    )
    (net (code "67") (name "VIN_UZ") (class "Default")
      (node (ref "X1") (pin "01") (pinfunction "01_01") (pintype "passive"))
      (node (ref "X1") (pin "02") (pinfunction "02_02") (pintype "passive"))
      (node (ref "X1") (pin "03") (pinfunction "03_03") (pintype "passive"))
      (node (ref "X1") (pin "04") (pinfunction "04_04") (pintype "passive"))
      (node (ref "X12") (pin "1") (pinfunction "1_1") (pintype "passive"))
      (node (ref "X2") (pin "01") (pinfunction "01_01") (pintype "passive"))
      (node (ref "X2") (pin "03") (pinfunction "03_03") (pintype "passive"))
      (node (ref "X4") (pin "1") (pinfunction "1_1") (pintype "passive"))
    )
    (net (code "68") (name "unconnected-(X4-Pad10)") (class "Default")
      (node (ref "X4") (pin "10") (pinfunction "10_10") (pintype "passive+no_connect"))
    )
    (net (code "69") (name "unconnected-(X8-Pad10)") (class "Default")
      (node (ref "X8") (pin "10") (pinfunction "10_10") (pintype "passive+no_connect"))
    )
  )
)
